# calculator.net
KiCad netlist of a schematic drawn in EAGLE
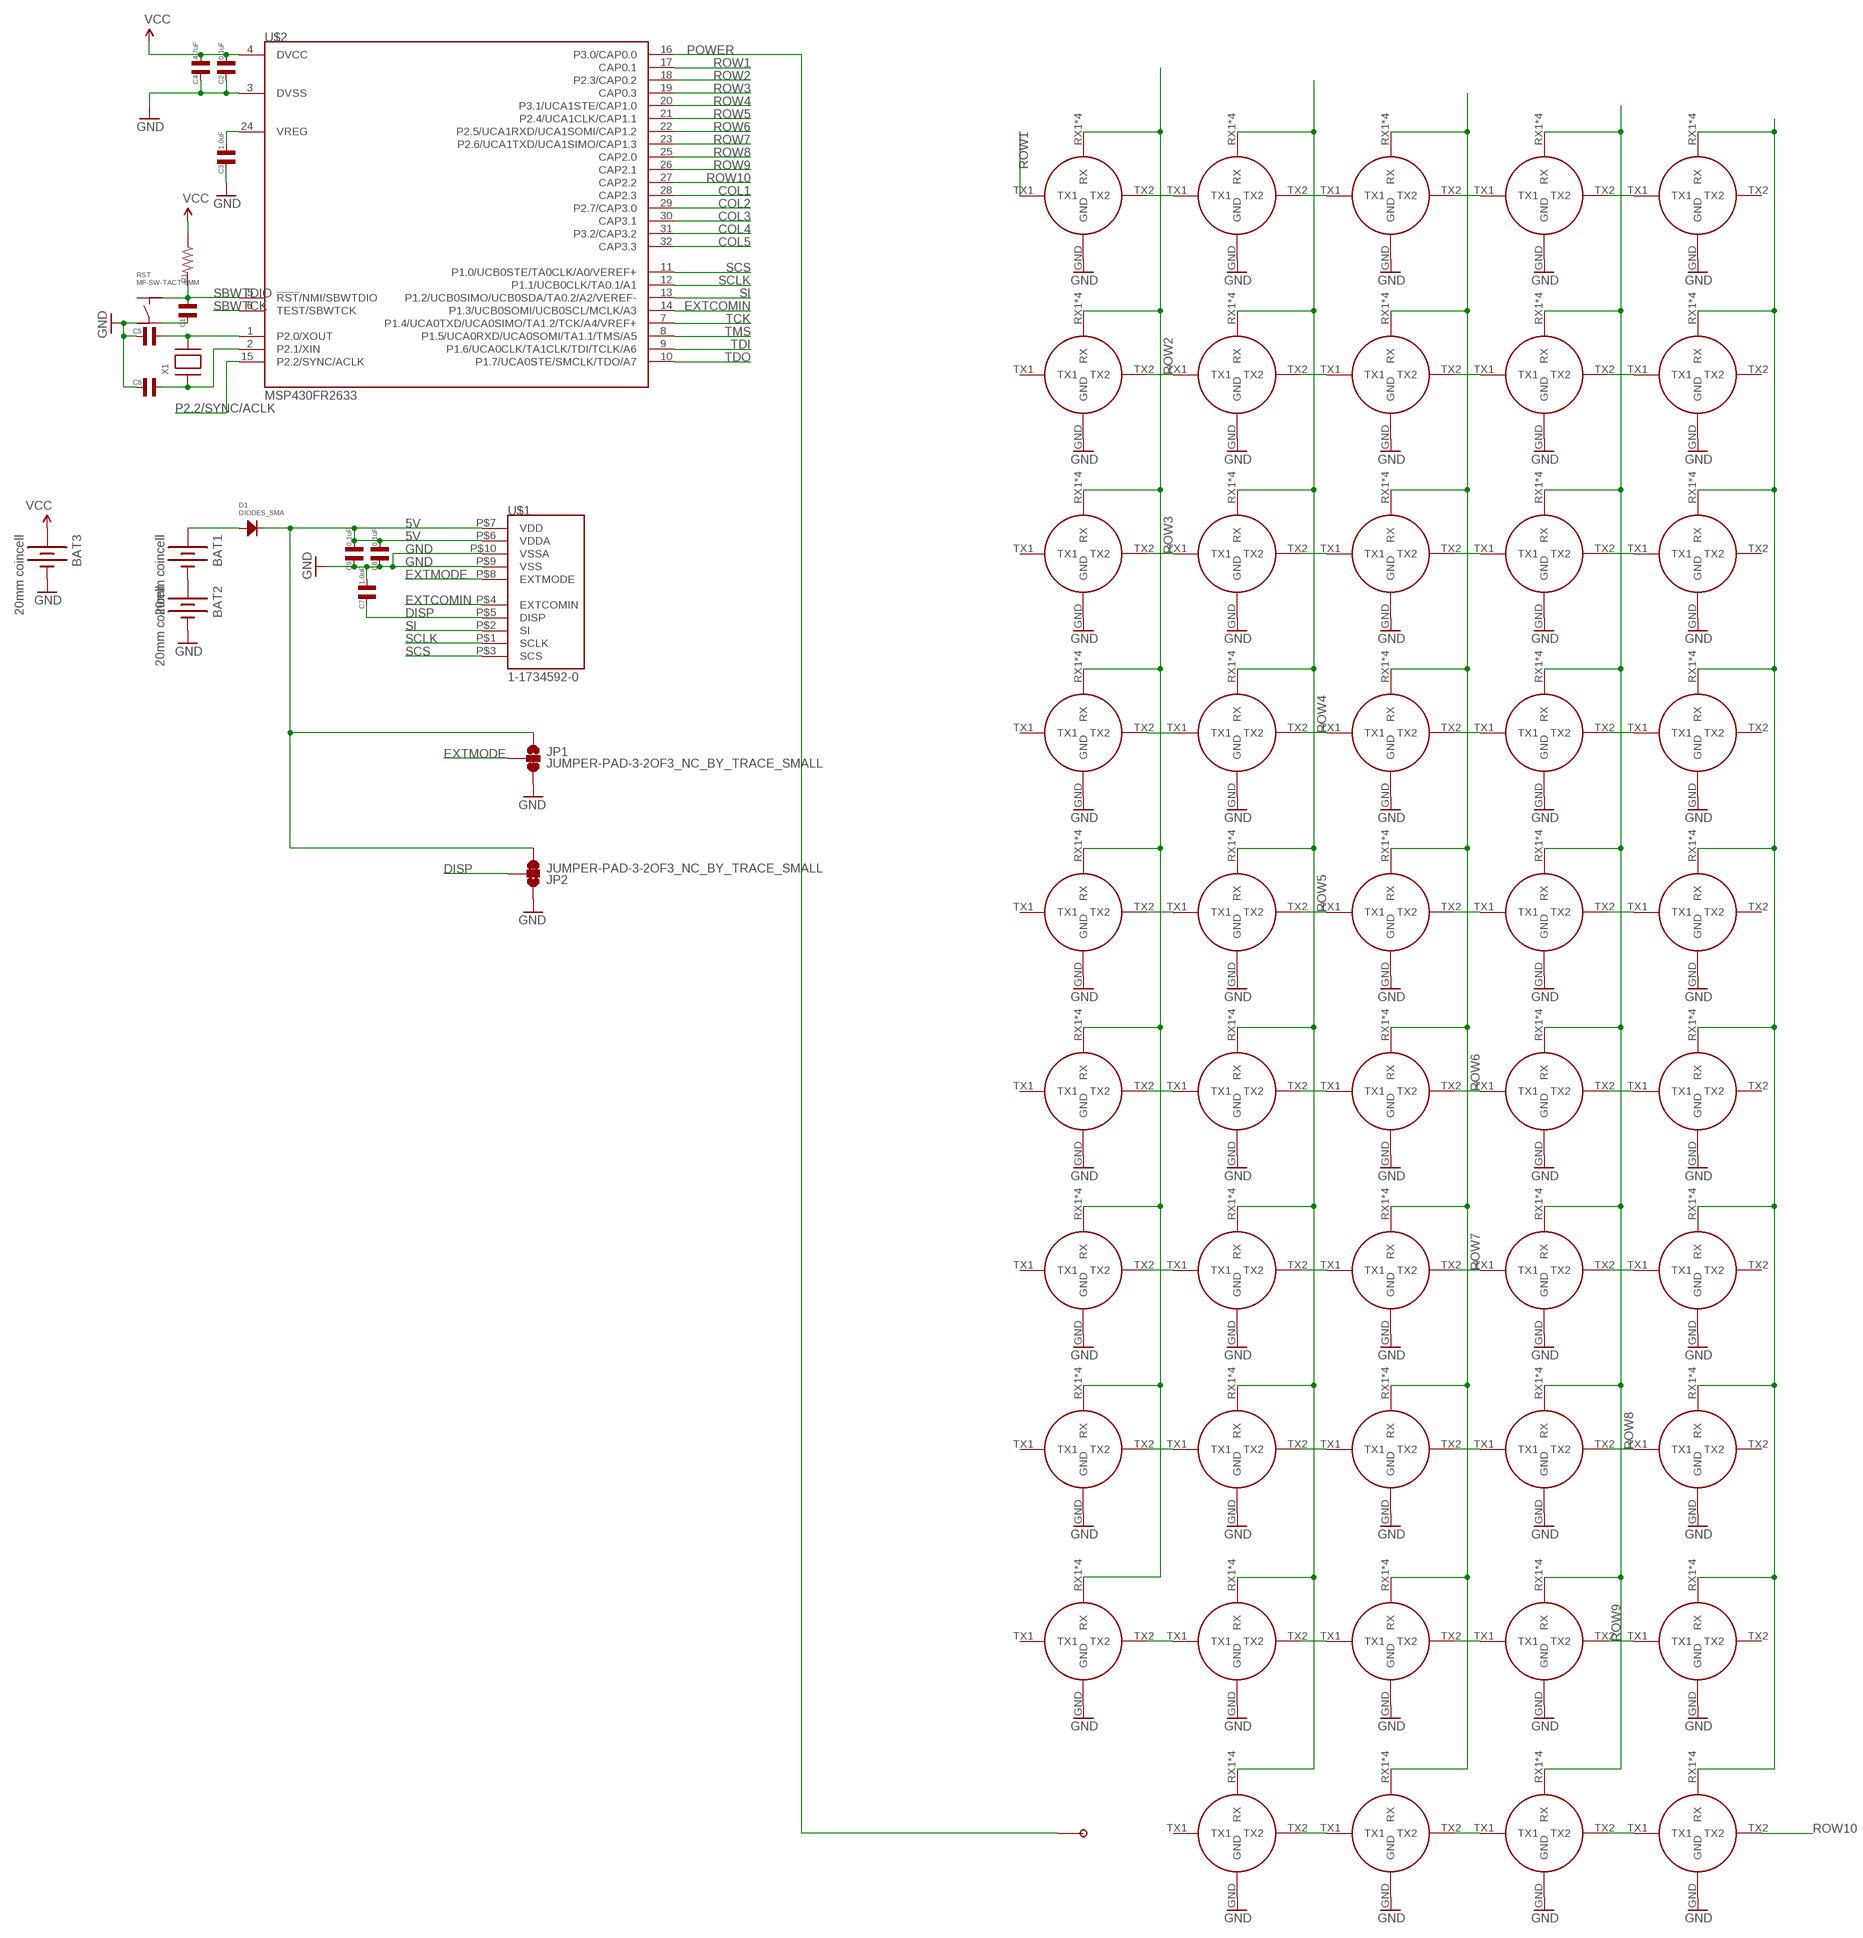
[diagram p0: schematic, sheet 1]

(export (version "E")
  (design (tool "Eeschema 10.0.6"))
  (components
    (comp (ref "BAT1")
      (value "20mm coincell")
      (footprint "eagle-import:BATTCON_20MM_4LEGS")
      (libsource (lib "eagle-import") (part "BATTERY20MM_4LEGS"))
    )
    (comp (ref "BAT2")
      (value "20mm coincell")
      (footprint "eagle-import:BATTCON_20MM_4LEGS")
      (libsource (lib "eagle-import") (part "BATTERY20MM_4LEGS"))
    )
    (comp (ref "BAT3")
      (value "20mm coincell")
      (footprint "eagle-import:BATTCON_20MM_4LEGS")
      (libsource (lib "eagle-import") (part "BATTERY20MM_4LEGS"))
    )
    (comp (ref "C1")
      (value "CAPACITOR_NP_0603")
      (footprint "eagle-import:C0603")
      (libsource (lib "eagle-import") (part "CAPACITOR_NP_0603"))
    )
    (comp (ref "C2")
      (value "0.1uF")
      (footprint "eagle-import:C0603")
      (libsource (lib "eagle-import") (part "CAPACITOR_NP_0603"))
    )
    (comp (ref "C3")
      (value "1.0uF")
      (footprint "eagle-import:C0603")
      (libsource (lib "eagle-import") (part "CAPACITOR_NP_0603"))
    )
    (comp (ref "C4")
      (value "4.7uF")
      (footprint "eagle-import:C0603")
      (libsource (lib "eagle-import") (part "CAPACITOR_NP_0603"))
    )
    (comp (ref "C5")
      (value "CAPACITOR_NP_0402")
      (footprint "eagle-import:C0402")
      (libsource (lib "eagle-import") (part "CAPACITOR_NP_0402"))
    )
    (comp (ref "C6")
      (value "CAPACITOR_NP_0402")
      (footprint "eagle-import:C0402")
      (libsource (lib "eagle-import") (part "CAPACITOR_NP_0402"))
    )
    (comp (ref "C7")
      (value "1.0uF")
      (footprint "eagle-import:C0603")
      (libsource (lib "eagle-import") (part "CAPACITOR_NP_0603"))
    )
    (comp (ref "C8")
      (value "0.1uF")
      (footprint "eagle-import:C0603")
      (libsource (lib "eagle-import") (part "CAPACITOR_NP_0603"))
    )
    (comp (ref "C9")
      (value "0.1uF")
      (footprint "eagle-import:C0603")
      (libsource (lib "eagle-import") (part "CAPACITOR_NP_0603"))
    )
    (comp (ref "D1")
      (value "DIODES_SMA")
      (footprint "eagle-import:SMA")
      (fields (field (name "HOUSEPART") "NO"))
      (libsource (lib "eagle-import") (part "DIODES_SMA"))
    )
    (comp (ref "JP1")
      (value "JUMPER-PAD-3-2OF3_NC_BY_TRACE_SMALL")
      (footprint "eagle-import:PAD-JUMPER-3-2OF3_NC_BY_TRACE_YES_SILK_FULL_BOX")
      (libsource (lib "eagle-import") (part "JUMPER-PAD-3-2OF3_NC_BY_TRACE_SMALL"))
    )
    (comp (ref "JP2")
      (value "JUMPER-PAD-3-2OF3_NC_BY_TRACE_SMALL")
      (footprint "eagle-import:PAD-JUMPER-3-2OF3_NC_BY_TRACE_YES_SILK_FULL_BOX")
      (libsource (lib "eagle-import") (part "JUMPER-PAD-3-2OF3_NC_BY_TRACE_SMALL"))
    )
    (comp (ref "P1")
      (value "CAPPADPAD")
      (footprint "eagle-import:CAPTOUCHBTN2")
      (libsource (lib "eagle-import") (part "CAPPADPAD"))
    )
    (comp (ref "R1")
      (value "RESISTOR_0603")
      (footprint "eagle-import:R0603")
      (libsource (lib "eagle-import") (part "RESISTOR_0603"))
    )
    (comp (ref "RST")
      (value "MF-SW-TACT-6MM")
      (footprint "eagle-import:TACT6MM")
      (fields (field (name "HOUSEPART") "YES"))
      (libsource (lib "eagle-import") (part "TACT_6MM"))
    )
    (comp (ref "U$1")
      (value "1-1734592-0")
      (footprint "eagle-import:1-1734592-0")
      (libsource (lib "eagle-import") (part "1-1734592-0"))
    )
    (comp (ref "U$2")
      (value "MSP430FR2633")
      (footprint "eagle-import:TSSOP32")
      (libsource (lib "eagle-import") (part "MSP430FR2633"))
    )
    (comp (ref "U$3")
      (value "CAPTOUCH")
      (footprint "eagle-import:CAPTOUCHBTN")
      (libsource (lib "eagle-import") (part "CAPTOUCH"))
    )
    (comp (ref "U$4")
      (value "CAPTOUCH")
      (footprint "eagle-import:CAPTOUCHBTN")
      (libsource (lib "eagle-import") (part "CAPTOUCH"))
    )
    (comp (ref "U$5")
      (value "CAPTOUCH")
      (footprint "eagle-import:CAPTOUCHBTN")
      (libsource (lib "eagle-import") (part "CAPTOUCH"))
    )
    (comp (ref "U$6")
      (value "CAPTOUCH")
      (footprint "eagle-import:CAPTOUCHBTN")
      (libsource (lib "eagle-import") (part "CAPTOUCH"))
    )
    (comp (ref "U$7")
      (value "CAPTOUCH")
      (footprint "eagle-import:CAPTOUCHBTN")
      (libsource (lib "eagle-import") (part "CAPTOUCH"))
    )
    (comp (ref "U$8")
      (value "CAPTOUCH")
      (footprint "eagle-import:CAPTOUCHBTN")
      (libsource (lib "eagle-import") (part "CAPTOUCH"))
    )
    (comp (ref "U$9")
      (value "CAPTOUCH")
      (footprint "eagle-import:CAPTOUCHBTN")
      (libsource (lib "eagle-import") (part "CAPTOUCH"))
    )
    (comp (ref "U$10")
      (value "CAPTOUCH")
      (footprint "eagle-import:CAPTOUCHBTN")
      (libsource (lib "eagle-import") (part "CAPTOUCH"))
    )
    (comp (ref "U$11")
      (value "CAPTOUCH")
      (footprint "eagle-import:CAPTOUCHBTN")
      (libsource (lib "eagle-import") (part "CAPTOUCH"))
    )
    (comp (ref "U$12")
      (value "CAPTOUCH")
      (footprint "eagle-import:CAPTOUCHBTN")
      (libsource (lib "eagle-import") (part "CAPTOUCH"))
    )
    (comp (ref "U$13")
      (value "CAPTOUCH")
      (footprint "eagle-import:CAPTOUCHBTN")
      (libsource (lib "eagle-import") (part "CAPTOUCH"))
    )
    (comp (ref "U$14")
      (value "CAPTOUCH")
      (footprint "eagle-import:CAPTOUCHBTN")
      (libsource (lib "eagle-import") (part "CAPTOUCH"))
    )
    (comp (ref "U$15")
      (value "CAPTOUCH")
      (footprint "eagle-import:CAPTOUCHBTN")
      (libsource (lib "eagle-import") (part "CAPTOUCH"))
    )
    (comp (ref "U$16")
      (value "CAPTOUCH")
      (footprint "eagle-import:CAPTOUCHBTN")
      (libsource (lib "eagle-import") (part "CAPTOUCH"))
    )
    (comp (ref "U$17")
      (value "CAPTOUCH")
      (footprint "eagle-import:CAPTOUCHBTN")
      (libsource (lib "eagle-import") (part "CAPTOUCH"))
    )
    (comp (ref "U$18")
      (value "CAPTOUCH")
      (footprint "eagle-import:CAPTOUCHBTN")
      (libsource (lib "eagle-import") (part "CAPTOUCH"))
    )
    (comp (ref "U$19")
      (value "CAPTOUCH")
      (footprint "eagle-import:CAPTOUCHBTN")
      (libsource (lib "eagle-import") (part "CAPTOUCH"))
    )
    (comp (ref "U$20")
      (value "CAPTOUCH")
      (footprint "eagle-import:CAPTOUCHBTN")
      (libsource (lib "eagle-import") (part "CAPTOUCH"))
    )
    (comp (ref "U$21")
      (value "CAPTOUCH")
      (footprint "eagle-import:CAPTOUCHBTN")
      (libsource (lib "eagle-import") (part "CAPTOUCH"))
    )
    (comp (ref "U$22")
      (value "CAPTOUCH")
      (footprint "eagle-import:CAPTOUCHBTN")
      (libsource (lib "eagle-import") (part "CAPTOUCH"))
    )
    (comp (ref "U$23")
      (value "CAPTOUCH")
      (footprint "eagle-import:CAPTOUCHBTN")
      (libsource (lib "eagle-import") (part "CAPTOUCH"))
    )
    (comp (ref "U$24")
      (value "CAPTOUCH")
      (footprint "eagle-import:CAPTOUCHBTN")
      (libsource (lib "eagle-import") (part "CAPTOUCH"))
    )
    (comp (ref "U$25")
      (value "CAPTOUCH")
      (footprint "eagle-import:CAPTOUCHBTN")
      (libsource (lib "eagle-import") (part "CAPTOUCH"))
    )
    (comp (ref "U$26")
      (value "CAPTOUCH")
      (footprint "eagle-import:CAPTOUCHBTN")
      (libsource (lib "eagle-import") (part "CAPTOUCH"))
    )
    (comp (ref "U$27")
      (value "CAPTOUCH")
      (footprint "eagle-import:CAPTOUCHBTN")
      (libsource (lib "eagle-import") (part "CAPTOUCH"))
    )
    (comp (ref "U$28")
      (value "CAPTOUCH")
      (footprint "eagle-import:CAPTOUCHBTN")
      (libsource (lib "eagle-import") (part "CAPTOUCH"))
    )
    (comp (ref "U$29")
      (value "CAPTOUCH")
      (footprint "eagle-import:CAPTOUCHBTN")
      (libsource (lib "eagle-import") (part "CAPTOUCH"))
    )
    (comp (ref "U$30")
      (value "CAPTOUCH")
      (footprint "eagle-import:CAPTOUCHBTN")
      (libsource (lib "eagle-import") (part "CAPTOUCH"))
    )
    (comp (ref "U$31")
      (value "CAPTOUCH")
      (footprint "eagle-import:CAPTOUCHBTN")
      (libsource (lib "eagle-import") (part "CAPTOUCH"))
    )
    (comp (ref "U$32")
      (value "CAPTOUCH")
      (footprint "eagle-import:CAPTOUCHBTN")
      (libsource (lib "eagle-import") (part "CAPTOUCH"))
    )
    (comp (ref "U$33")
      (value "CAPTOUCH")
      (footprint "eagle-import:CAPTOUCHBTN")
      (libsource (lib "eagle-import") (part "CAPTOUCH"))
    )
    (comp (ref "U$34")
      (value "CAPTOUCH")
      (footprint "eagle-import:CAPTOUCHBTN")
      (libsource (lib "eagle-import") (part "CAPTOUCH"))
    )
    (comp (ref "U$35")
      (value "CAPTOUCH")
      (footprint "eagle-import:CAPTOUCHBTN")
      (libsource (lib "eagle-import") (part "CAPTOUCH"))
    )
    (comp (ref "U$36")
      (value "CAPTOUCH")
      (footprint "eagle-import:CAPTOUCHBTN")
      (libsource (lib "eagle-import") (part "CAPTOUCH"))
    )
    (comp (ref "U$37")
      (value "CAPTOUCH")
      (footprint "eagle-import:CAPTOUCHBTN")
      (libsource (lib "eagle-import") (part "CAPTOUCH"))
    )
    (comp (ref "U$38")
      (value "CAPTOUCH")
      (footprint "eagle-import:CAPTOUCHBTN")
      (libsource (lib "eagle-import") (part "CAPTOUCH"))
    )
    (comp (ref "U$39")
      (value "CAPTOUCH")
      (footprint "eagle-import:CAPTOUCHBTN")
      (libsource (lib "eagle-import") (part "CAPTOUCH"))
    )
    (comp (ref "U$40")
      (value "CAPTOUCH")
      (footprint "eagle-import:CAPTOUCHBTN")
      (libsource (lib "eagle-import") (part "CAPTOUCH"))
    )
    (comp (ref "U$41")
      (value "CAPTOUCH")
      (footprint "eagle-import:CAPTOUCHBTN")
      (libsource (lib "eagle-import") (part "CAPTOUCH"))
    )
    (comp (ref "U$42")
      (value "CAPTOUCH")
      (footprint "eagle-import:CAPTOUCHBTN")
      (libsource (lib "eagle-import") (part "CAPTOUCH"))
    )
    (comp (ref "U$43")
      (value "CAPTOUCH")
      (footprint "eagle-import:CAPTOUCHBTN")
      (libsource (lib "eagle-import") (part "CAPTOUCH"))
    )
    (comp (ref "U$44")
      (value "CAPTOUCH")
      (footprint "eagle-import:CAPTOUCHBTN")
      (libsource (lib "eagle-import") (part "CAPTOUCH"))
    )
    (comp (ref "U$45")
      (value "CAPTOUCH")
      (footprint "eagle-import:CAPTOUCHBTN")
      (libsource (lib "eagle-import") (part "CAPTOUCH"))
    )
    (comp (ref "U$46")
      (value "CAPTOUCH")
      (footprint "eagle-import:CAPTOUCHBTN")
      (libsource (lib "eagle-import") (part "CAPTOUCH"))
    )
    (comp (ref "U$47")
      (value "CAPTOUCH")
      (footprint "eagle-import:CAPTOUCHBTN")
      (libsource (lib "eagle-import") (part "CAPTOUCH"))
    )
    (comp (ref "U$48")
      (value "CAPTOUCH")
      (footprint "eagle-import:CAPTOUCHBTN")
      (libsource (lib "eagle-import") (part "CAPTOUCH"))
    )
    (comp (ref "U$49")
      (value "CAPTOUCH")
      (footprint "eagle-import:CAPTOUCHBTN")
      (libsource (lib "eagle-import") (part "CAPTOUCH"))
    )
    (comp (ref "U$50")
      (value "CAPTOUCH")
      (footprint "eagle-import:CAPTOUCHBTN")
      (libsource (lib "eagle-import") (part "CAPTOUCH"))
    )
    (comp (ref "U$51")
      (value "CAPTOUCH")
      (footprint "eagle-import:CAPTOUCHBTN")
      (libsource (lib "eagle-import") (part "CAPTOUCH"))
    )
    (comp (ref "X1")
      (value "XTAL-3.2X1.5")
      (footprint "eagle-import:XTAL3215")
      (libsource (lib "eagle-import") (part "XTAL-3.2X1.5"))
    )
  )
  (nets
    (net (code "1") (name "/5V") (class "Default")
      (node (ref "C8") (pin "P$1") (pinfunction "P$1_P$1") (pintype "passive"))
      (node (ref "C9") (pin "P$1") (pinfunction "P$1_P$1") (pintype "passive"))
      (node (ref "D1") (pin "CATHODE") (pinfunction "CATHODE_CATHODE") (pintype "bidirectional"))
      (node (ref "JP1") (pin "1") (pinfunction "1_1") (pintype "passive"))
      (node (ref "JP2") (pin "3") (pinfunction "3_3") (pintype "passive"))
      (node (ref "U$1") (pin "P$6") (pinfunction "VDDA_P$6") (pintype "bidirectional"))
      (node (ref "U$1") (pin "P$7") (pinfunction "VDD_P$7") (pintype "bidirectional"))
    )
    (net (code "2") (name "/COL1") (class "Default")
      (node (ref "U$13") (pin "RX1") (pinfunction "RX_RX1") (pintype "bidirectional"))
      (node (ref "U$13") (pin "RX2") (pinfunction "RX_RX2") (pintype "bidirectional"))
      (node (ref "U$13") (pin "RX3") (pinfunction "RX_RX3") (pintype "bidirectional"))
      (node (ref "U$13") (pin "RX4") (pinfunction "RX_RX4") (pintype "bidirectional"))
      (node (ref "U$18") (pin "RX1") (pinfunction "RX_RX1") (pintype "bidirectional"))
      (node (ref "U$18") (pin "RX2") (pinfunction "RX_RX2") (pintype "bidirectional"))
      (node (ref "U$18") (pin "RX3") (pinfunction "RX_RX3") (pintype "bidirectional"))
      (node (ref "U$18") (pin "RX4") (pinfunction "RX_RX4") (pintype "bidirectional"))
      (node (ref "U$2") (pin "28") (pinfunction "CAP2.3_28") (pintype "bidirectional"))
      (node (ref "U$23") (pin "RX1") (pinfunction "RX_RX1") (pintype "bidirectional"))
      (node (ref "U$23") (pin "RX2") (pinfunction "RX_RX2") (pintype "bidirectional"))
      (node (ref "U$23") (pin "RX3") (pinfunction "RX_RX3") (pintype "bidirectional"))
      (node (ref "U$23") (pin "RX4") (pinfunction "RX_RX4") (pintype "bidirectional"))
      (node (ref "U$28") (pin "RX1") (pinfunction "RX_RX1") (pintype "bidirectional"))
      (node (ref "U$28") (pin "RX2") (pinfunction "RX_RX2") (pintype "bidirectional"))
      (node (ref "U$28") (pin "RX3") (pinfunction "RX_RX3") (pintype "bidirectional"))
      (node (ref "U$28") (pin "RX4") (pinfunction "RX_RX4") (pintype "bidirectional"))
      (node (ref "U$3") (pin "RX1") (pinfunction "RX_RX1") (pintype "bidirectional"))
      (node (ref "U$3") (pin "RX2") (pinfunction "RX_RX2") (pintype "bidirectional"))
      (node (ref "U$3") (pin "RX3") (pinfunction "RX_RX3") (pintype "bidirectional"))
      (node (ref "U$3") (pin "RX4") (pinfunction "RX_RX4") (pintype "bidirectional"))
      (node (ref "U$33") (pin "RX1") (pinfunction "RX_RX1") (pintype "bidirectional"))
      (node (ref "U$33") (pin "RX2") (pinfunction "RX_RX2") (pintype "bidirectional"))
      (node (ref "U$33") (pin "RX3") (pinfunction "RX_RX3") (pintype "bidirectional"))
      (node (ref "U$33") (pin "RX4") (pinfunction "RX_RX4") (pintype "bidirectional"))
      (node (ref "U$38") (pin "RX1") (pinfunction "RX_RX1") (pintype "bidirectional"))
      (node (ref "U$38") (pin "RX2") (pinfunction "RX_RX2") (pintype "bidirectional"))
      (node (ref "U$38") (pin "RX3") (pinfunction "RX_RX3") (pintype "bidirectional"))
      (node (ref "U$38") (pin "RX4") (pinfunction "RX_RX4") (pintype "bidirectional"))
      (node (ref "U$43") (pin "RX1") (pinfunction "RX_RX1") (pintype "bidirectional"))
      (node (ref "U$43") (pin "RX2") (pinfunction "RX_RX2") (pintype "bidirectional"))
      (node (ref "U$43") (pin "RX3") (pinfunction "RX_RX3") (pintype "bidirectional"))
      (node (ref "U$43") (pin "RX4") (pinfunction "RX_RX4") (pintype "bidirectional"))
      (node (ref "U$8") (pin "RX1") (pinfunction "RX_RX1") (pintype "bidirectional"))
      (node (ref "U$8") (pin "RX2") (pinfunction "RX_RX2") (pintype "bidirectional"))
      (node (ref "U$8") (pin "RX3") (pinfunction "RX_RX3") (pintype "bidirectional"))
      (node (ref "U$8") (pin "RX4") (pinfunction "RX_RX4") (pintype "bidirectional"))
    )
    (net (code "3") (name "/COL2") (class "Default")
      (node (ref "U$14") (pin "RX1") (pinfunction "RX_RX1") (pintype "bidirectional"))
      (node (ref "U$14") (pin "RX2") (pinfunction "RX_RX2") (pintype "bidirectional"))
      (node (ref "U$14") (pin "RX3") (pinfunction "RX_RX3") (pintype "bidirectional"))
      (node (ref "U$14") (pin "RX4") (pinfunction "RX_RX4") (pintype "bidirectional"))
      (node (ref "U$19") (pin "RX1") (pinfunction "RX_RX1") (pintype "bidirectional"))
      (node (ref "U$19") (pin "RX2") (pinfunction "RX_RX2") (pintype "bidirectional"))
      (node (ref "U$19") (pin "RX3") (pinfunction "RX_RX3") (pintype "bidirectional"))
      (node (ref "U$19") (pin "RX4") (pinfunction "RX_RX4") (pintype "bidirectional"))
      (node (ref "U$2") (pin "29") (pinfunction "P2.7/CAP3.0_29") (pintype "bidirectional"))
      (node (ref "U$24") (pin "RX1") (pinfunction "RX_RX1") (pintype "bidirectional"))
      (node (ref "U$24") (pin "RX2") (pinfunction "RX_RX2") (pintype "bidirectional"))
      (node (ref "U$24") (pin "RX3") (pinfunction "RX_RX3") (pintype "bidirectional"))
      (node (ref "U$24") (pin "RX4") (pinfunction "RX_RX4") (pintype "bidirectional"))
      (node (ref "U$29") (pin "RX1") (pinfunction "RX_RX1") (pintype "bidirectional"))
      (node (ref "U$29") (pin "RX2") (pinfunction "RX_RX2") (pintype "bidirectional"))
      (node (ref "U$29") (pin "RX3") (pinfunction "RX_RX3") (pintype "bidirectional"))
      (node (ref "U$29") (pin "RX4") (pinfunction "RX_RX4") (pintype "bidirectional"))
      (node (ref "U$34") (pin "RX1") (pinfunction "RX_RX1") (pintype "bidirectional"))
      (node (ref "U$34") (pin "RX2") (pinfunction "RX_RX2") (pintype "bidirectional"))
      (node (ref "U$34") (pin "RX3") (pinfunction "RX_RX3") (pintype "bidirectional"))
      (node (ref "U$34") (pin "RX4") (pinfunction "RX_RX4") (pintype "bidirectional"))
      (node (ref "U$39") (pin "RX1") (pinfunction "RX_RX1") (pintype "bidirectional"))
      (node (ref "U$39") (pin "RX2") (pinfunction "RX_RX2") (pintype "bidirectional"))
      (node (ref "U$39") (pin "RX3") (pinfunction "RX_RX3") (pintype "bidirectional"))
      (node (ref "U$39") (pin "RX4") (pinfunction "RX_RX4") (pintype "bidirectional"))
      (node (ref "U$4") (pin "RX1") (pinfunction "RX_RX1") (pintype "bidirectional"))
      (node (ref "U$4") (pin "RX2") (pinfunction "RX_RX2") (pintype "bidirectional"))
      (node (ref "U$4") (pin "RX3") (pinfunction "RX_RX3") (pintype "bidirectional"))
      (node (ref "U$4") (pin "RX4") (pinfunction "RX_RX4") (pintype "bidirectional"))
      (node (ref "U$44") (pin "RX1") (pinfunction "RX_RX1") (pintype "bidirectional"))
      (node (ref "U$44") (pin "RX2") (pinfunction "RX_RX2") (pintype "bidirectional"))
      (node (ref "U$44") (pin "RX3") (pinfunction "RX_RX3") (pintype "bidirectional"))
      (node (ref "U$44") (pin "RX4") (pinfunction "RX_RX4") (pintype "bidirectional"))
      (node (ref "U$48") (pin "RX1") (pinfunction "RX_RX1") (pintype "bidirectional"))
      (node (ref "U$48") (pin "RX2") (pinfunction "RX_RX2") (pintype "bidirectional"))
      (node (ref "U$48") (pin "RX3") (pinfunction "RX_RX3") (pintype "bidirectional"))
      (node (ref "U$48") (pin "RX4") (pinfunction "RX_RX4") (pintype "bidirectional"))
      (node (ref "U$9") (pin "RX1") (pinfunction "RX_RX1") (pintype "bidirectional"))
      (node (ref "U$9") (pin "RX2") (pinfunction "RX_RX2") (pintype "bidirectional"))
      (node (ref "U$9") (pin "RX3") (pinfunction "RX_RX3") (pintype "bidirectional"))
      (node (ref "U$9") (pin "RX4") (pinfunction "RX_RX4") (pintype "bidirectional"))
    )
    (net (code "4") (name "/COL3") (class "Default")
      (node (ref "U$10") (pin "RX1") (pinfunction "RX_RX1") (pintype "bidirectional"))
      (node (ref "U$10") (pin "RX2") (pinfunction "RX_RX2") (pintype "bidirectional"))
      (node (ref "U$10") (pin "RX3") (pinfunction "RX_RX3") (pintype "bidirectional"))
      (node (ref "U$10") (pin "RX4") (pinfunction "RX_RX4") (pintype "bidirectional"))
      (node (ref "U$15") (pin "RX1") (pinfunction "RX_RX1") (pintype "bidirectional"))
      (node (ref "U$15") (pin "RX2") (pinfunction "RX_RX2") (pintype "bidirectional"))
      (node (ref "U$15") (pin "RX3") (pinfunction "RX_RX3") (pintype "bidirectional"))
      (node (ref "U$15") (pin "RX4") (pinfunction "RX_RX4") (pintype "bidirectional"))
      (node (ref "U$2") (pin "30") (pinfunction "CAP3.1_30") (pintype "bidirectional"))
      (node (ref "U$20") (pin "RX1") (pinfunction "RX_RX1") (pintype "bidirectional"))
      (node (ref "U$20") (pin "RX2") (pinfunction "RX_RX2") (pintype "bidirectional"))
      (node (ref "U$20") (pin "RX3") (pinfunction "RX_RX3") (pintype "bidirectional"))
      (node (ref "U$20") (pin "RX4") (pinfunction "RX_RX4") (pintype "bidirectional"))
      (node (ref "U$25") (pin "RX1") (pinfunction "RX_RX1") (pintype "bidirectional"))
      (node (ref "U$25") (pin "RX2") (pinfunction "RX_RX2") (pintype "bidirectional"))
      (node (ref "U$25") (pin "RX3") (pinfunction "RX_RX3") (pintype "bidirectional"))
      (node (ref "U$25") (pin "RX4") (pinfunction "RX_RX4") (pintype "bidirectional"))
      (node (ref "U$30") (pin "RX1") (pinfunction "RX_RX1") (pintype "bidirectional"))
      (node (ref "U$30") (pin "RX2") (pinfunction "RX_RX2") (pintype "bidirectional"))
      (node (ref "U$30") (pin "RX3") (pinfunction "RX_RX3") (pintype "bidirectional"))
      (node (ref "U$30") (pin "RX4") (pinfunction "RX_RX4") (pintype "bidirectional"))
      (node (ref "U$35") (pin "RX1") (pinfunction "RX_RX1") (pintype "bidirectional"))
      (node (ref "U$35") (pin "RX2") (pinfunction "RX_RX2") (pintype "bidirectional"))
      (node (ref "U$35") (pin "RX3") (pinfunction "RX_RX3") (pintype "bidirectional"))
      (node (ref "U$35") (pin "RX4") (pinfunction "RX_RX4") (pintype "bidirectional"))
      (node (ref "U$40") (pin "RX1") (pinfunction "RX_RX1") (pintype "bidirectional"))
      (node (ref "U$40") (pin "RX2") (pinfunction "RX_RX2") (pintype "bidirectional"))
      (node (ref "U$40") (pin "RX3") (pinfunction "RX_RX3") (pintype "bidirectional"))
      (node (ref "U$40") (pin "RX4") (pinfunction "RX_RX4") (pintype "bidirectional"))
      (node (ref "U$45") (pin "RX1") (pinfunction "RX_RX1") (pintype "bidirectional"))
      (node (ref "U$45") (pin "RX2") (pinfunction "RX_RX2") (pintype "bidirectional"))
      (node (ref "U$45") (pin "RX3") (pinfunction "RX_RX3") (pintype "bidirectional"))
      (node (ref "U$45") (pin "RX4") (pinfunction "RX_RX4") (pintype "bidirectional"))
      (node (ref "U$49") (pin "RX1") (pinfunction "RX_RX1") (pintype "bidirectional"))
      (node (ref "U$49") (pin "RX2") (pinfunction "RX_RX2") (pintype "bidirectional"))
      (node (ref "U$49") (pin "RX3") (pinfunction "RX_RX3") (pintype "bidirectional"))
      (node (ref "U$49") (pin "RX4") (pinfunction "RX_RX4") (pintype "bidirectional"))
      (node (ref "U$5") (pin "RX1") (pinfunction "RX_RX1") (pintype "bidirectional"))
      (node (ref "U$5") (pin "RX2") (pinfunction "RX_RX2") (pintype "bidirectional"))
      (node (ref "U$5") (pin "RX3") (pinfunction "RX_RX3") (pintype "bidirectional"))
      (node (ref "U$5") (pin "RX4") (pinfunction "RX_RX4") (pintype "bidirectional"))
    )
    (net (code "5") (name "/COL4") (class "Default")
      (node (ref "U$11") (pin "RX1") (pinfunction "RX_RX1") (pintype "bidirectional"))
      (node (ref "U$11") (pin "RX2") (pinfunction "RX_RX2") (pintype "bidirectional"))
      (node (ref "U$11") (pin "RX3") (pinfunction "RX_RX3") (pintype "bidirectional"))
      (node (ref "U$11") (pin "RX4") (pinfunction "RX_RX4") (pintype "bidirectional"))
      (node (ref "U$16") (pin "RX1") (pinfunction "RX_RX1") (pintype "bidirectional"))
      (node (ref "U$16") (pin "RX2") (pinfunction "RX_RX2") (pintype "bidirectional"))
      (node (ref "U$16") (pin "RX3") (pinfunction "RX_RX3") (pintype "bidirectional"))
      (node (ref "U$16") (pin "RX4") (pinfunction "RX_RX4") (pintype "bidirectional"))
      (node (ref "U$2") (pin "31") (pinfunction "P3.2/CAP3.2_31") (pintype "bidirectional"))
      (node (ref "U$21") (pin "RX1") (pinfunction "RX_RX1") (pintype "bidirectional"))
      (node (ref "U$21") (pin "RX2") (pinfunction "RX_RX2") (pintype "bidirectional"))
      (node (ref "U$21") (pin "RX3") (pinfunction "RX_RX3") (pintype "bidirectional"))
      (node (ref "U$21") (pin "RX4") (pinfunction "RX_RX4") (pintype "bidirectional"))
      (node (ref "U$26") (pin "RX1") (pinfunction "RX_RX1") (pintype "bidirectional"))
      (node (ref "U$26") (pin "RX2") (pinfunction "RX_RX2") (pintype "bidirectional"))
      (node (ref "U$26") (pin "RX3") (pinfunction "RX_RX3") (pintype "bidirectional"))
      (node (ref "U$26") (pin "RX4") (pinfunction "RX_RX4") (pintype "bidirectional"))
      (node (ref "U$31") (pin "RX1") (pinfunction "RX_RX1") (pintype "bidirectional"))
      (node (ref "U$31") (pin "RX2") (pinfunction "RX_RX2") (pintype "bidirectional"))
      (node (ref "U$31") (pin "RX3") (pinfunction "RX_RX3") (pintype "bidirectional"))
      (node (ref "U$31") (pin "RX4") (pinfunction "RX_RX4") (pintype "bidirectional"))
      (node (ref "U$36") (pin "RX1") (pinfunction "RX_RX1") (pintype "bidirectional"))
      (node (ref "U$36") (pin "RX2") (pinfunction "RX_RX2") (pintype "bidirectional"))
      (node (ref "U$36") (pin "RX3") (pinfunction "RX_RX3") (pintype "bidirectional"))
      (node (ref "U$36") (pin "RX4") (pinfunction "RX_RX4") (pintype "bidirectional"))
      (node (ref "U$41") (pin "RX1") (pinfunction "RX_RX1") (pintype "bidirectional"))
      (node (ref "U$41") (pin "RX2") (pinfunction "RX_RX2") (pintype "bidirectional"))
      (node (ref "U$41") (pin "RX3") (pinfunction "RX_RX3") (pintype "bidirectional"))
      (node (ref "U$41") (pin "RX4") (pinfunction "RX_RX4") (pintype "bidirectional"))
      (node (ref "U$46") (pin "RX1") (pinfunction "RX_RX1") (pintype "bidirectional"))
      (node (ref "U$46") (pin "RX2") (pinfunction "RX_RX2") (pintype "bidirectional"))
      (node (ref "U$46") (pin "RX3") (pinfunction "RX_RX3") (pintype "bidirectional"))
      (node (ref "U$46") (pin "RX4") (pinfunction "RX_RX4") (pintype "bidirectional"))
      (node (ref "U$50") (pin "RX1") (pinfunction "RX_RX1") (pintype "bidirectional"))
      (node (ref "U$50") (pin "RX2") (pinfunction "RX_RX2") (pintype "bidirectional"))
      (node (ref "U$50") (pin "RX3") (pinfunction "RX_RX3") (pintype "bidirectional"))
      (node (ref "U$50") (pin "RX4") (pinfunction "RX_RX4") (pintype "bidirectional"))
      (node (ref "U$6") (pin "RX1") (pinfunction "RX_RX1") (pintype "bidirectional"))
      (node (ref "U$6") (pin "RX2") (pinfunction "RX_RX2") (pintype "bidirectional"))
      (node (ref "U$6") (pin "RX3") (pinfunction "RX_RX3") (pintype "bidirectional"))
      (node (ref "U$6") (pin "RX4") (pinfunction "RX_RX4") (pintype "bidirectional"))
    )
    (net (code "6") (name "/COL5") (class "Default")
      (node (ref "U$12") (pin "RX1") (pinfunction "RX_RX1") (pintype "bidirectional"))
      (node (ref "U$12") (pin "RX2") (pinfunction "RX_RX2") (pintype "bidirectional"))
      (node (ref "U$12") (pin "RX3") (pinfunction "RX_RX3") (pintype "bidirectional"))
      (node (ref "U$12") (pin "RX4") (pinfunction "RX_RX4") (pintype "bidirectional"))
      (node (ref "U$17") (pin "RX1") (pinfunction "RX_RX1") (pintype "bidirectional"))
      (node (ref "U$17") (pin "RX2") (pinfunction "RX_RX2") (pintype "bidirectional"))
      (node (ref "U$17") (pin "RX3") (pinfunction "RX_RX3") (pintype "bidirectional"))
      (node (ref "U$17") (pin "RX4") (pinfunction "RX_RX4") (pintype "bidirectional"))
      (node (ref "U$2") (pin "32") (pinfunction "CAP3.3_32") (pintype "bidirectional"))
      (node (ref "U$22") (pin "RX1") (pinfunction "RX_RX1") (pintype "bidirectional"))
      (node (ref "U$22") (pin "RX2") (pinfunction "RX_RX2") (pintype "bidirectional"))
      (node (ref "U$22") (pin "RX3") (pinfunction "RX_RX3") (pintype "bidirectional"))
      (node (ref "U$22") (pin "RX4") (pinfunction "RX_RX4") (pintype "bidirectional"))
      (node (ref "U$27") (pin "RX1") (pinfunction "RX_RX1") (pintype "bidirectional"))
      (node (ref "U$27") (pin "RX2") (pinfunction "RX_RX2") (pintype "bidirectional"))
      (node (ref "U$27") (pin "RX3") (pinfunction "RX_RX3") (pintype "bidirectional"))
      (node (ref "U$27") (pin "RX4") (pinfunction "RX_RX4") (pintype "bidirectional"))
      (node (ref "U$32") (pin "RX1") (pinfunction "RX_RX1") (pintype "bidirectional"))
      (node (ref "U$32") (pin "RX2") (pinfunction "RX_RX2") (pintype "bidirectional"))
      (node (ref "U$32") (pin "RX3") (pinfunction "RX_RX3") (pintype "bidirectional"))
      (node (ref "U$32") (pin "RX4") (pinfunction "RX_RX4") (pintype "bidirectional"))
      (node (ref "U$37") (pin "RX1") (pinfunction "RX_RX1") (pintype "bidirectional"))
      (node (ref "U$37") (pin "RX2") (pinfunction "RX_RX2") (pintype "bidirectional"))
      (node (ref "U$37") (pin "RX3") (pinfunction "RX_RX3") (pintype "bidirectional"))
      (node (ref "U$37") (pin "RX4") (pinfunction "RX_RX4") (pintype "bidirectional"))
      (node (ref "U$42") (pin "RX1") (pinfunction "RX_RX1") (pintype "bidirectional"))
      (node (ref "U$42") (pin "RX2") (pinfunction "RX_RX2") (pintype "bidirectional"))
      (node (ref "U$42") (pin "RX3") (pinfunction "RX_RX3") (pintype "bidirectional"))
      (node (ref "U$42") (pin "RX4") (pinfunction "RX_RX4") (pintype "bidirectional"))
      (node (ref "U$47") (pin "RX1") (pinfunction "RX_RX1") (pintype "bidirectional"))
      (node (ref "U$47") (pin "RX2") (pinfunction "RX_RX2") (pintype "bidirectional"))
      (node (ref "U$47") (pin "RX3") (pinfunction "RX_RX3") (pintype "bidirectional"))
      (node (ref "U$47") (pin "RX4") (pinfunction "RX_RX4") (pintype "bidirectional"))
      (node (ref "U$51") (pin "RX1") (pinfunction "RX_RX1") (pintype "bidirectional"))
      (node (ref "U$51") (pin "RX2") (pinfunction "RX_RX2") (pintype "bidirectional"))
      (node (ref "U$51") (pin "RX3") (pinfunction "RX_RX3") (pintype "bidirectional"))
      (node (ref "U$51") (pin "RX4") (pinfunction "RX_RX4") (pintype "bidirectional"))
      (node (ref "U$7") (pin "RX1") (pinfunction "RX_RX1") (pintype "bidirectional"))
      (node (ref "U$7") (pin "RX2") (pinfunction "RX_RX2") (pintype "bidirectional"))
      (node (ref "U$7") (pin "RX3") (pinfunction "RX_RX3") (pintype "bidirectional"))
      (node (ref "U$7") (pin "RX4") (pinfunction "RX_RX4") (pintype "bidirectional"))
    )
    (net (code "7") (name "/DISP") (class "Default")
      (node (ref "C7") (pin "P$2") (pinfunction "P$2_P$2") (pintype "passive"))
      (node (ref "JP2") (pin "2") (pinfunction "2_2") (pintype "passive"))
      (node (ref "U$1") (pin "P$5") (pinfunction "DISP_P$5") (pintype "bidirectional"))
    )
    (net (code "8") (name "/EXTCOMIN") (class "Default")
      (node (ref "U$1") (pin "P$4") (pinfunction "EXTCOMIN_P$4") (pintype "bidirectional"))
      (node (ref "U$2") (pin "14") (pinfunction "P1.3/UCB0SOMI/UCB0SCL/MCLK/A3_14") (pintype "bidirectional"))
    )
    (net (code "9") (name "/EXTMODE") (class "Default")
      (node (ref "JP1") (pin "2") (pinfunction "2_2") (pintype "passive"))
      (node (ref "U$1") (pin "P$8") (pinfunction "EXTMODE_P$8") (pintype "bidirectional"))
    )
    (net (code "10") (name "/P2.2{slash}SYNC{slash}ACLK") (class "Default")
      (node (ref "U$2") (pin "15") (pinfunction "P2.2/SYNC/ACLK_15") (pintype "bidirectional"))
    )
    (net (code "11") (name "/POWER") (class "Default")
      (node (ref "P1") (pin "RX") (pinfunction "P$1_RX") (pintype "bidirectional"))
      (node (ref "U$2") (pin "16") (pinfunction "P3.0/CAP0.0_16") (pintype "bidirectional"))
    )
    (net (code "12") (name "/ROW1") (class "Default")
      (node (ref "U$2") (pin "17") (pinfunction "CAP0.1_17") (pintype "bidirectional"))
      (node (ref "U$3") (pin "TX1") (pinfunction "TX1_TX1") (pintype "bidirectional"))
    )
    (net (code "13") (name "/ROW2") (class "Default")
      (node (ref "U$2") (pin "18") (pinfunction "P2.3/CAP0.2_18") (pintype "bidirectional"))
      (node (ref "U$8") (pin "TX2") (pinfunction "TX2_TX2") (pintype "bidirectional"))
      (node (ref "U$9") (pin "TX1") (pinfunction "TX1_TX1") (pintype "bidirectional"))
    )
    (net (code "14") (name "/ROW3") (class "Default")
      (node (ref "U$13") (pin "TX2") (pinfunction "TX2_TX2") (pintype "bidirectional"))
      (node (ref "U$14") (pin "TX1") (pinfunction "TX1_TX1") (pintype "bidirectional"))
      (node (ref "U$2") (pin "19") (pinfunction "CAP0.3_19") (pintype "bidirectional"))
    )
    (net (code "15") (name "/ROW4") (class "Default")
      (node (ref "U$19") (pin "TX2") (pinfunction "TX2_TX2") (pintype "bidirectional"))
      (node (ref "U$2") (pin "20") (pinfunction "P3.1/UCA1STE/CAP1.0_20") (pintype "bidirectional"))
      (node (ref "U$20") (pin "TX1") (pinfunction "TX1_TX1") (pintype "bidirectional"))
    )
    (net (code "16") (name "/ROW5") (class "Default")
      (node (ref "U$2") (pin "21") (pinfunction "P2.4/UCA1CLK/CAP1.1_21") (pintype "bidirectional"))
      (node (ref "U$24") (pin "TX2") (pinfunction "TX2_TX2") (pintype "bidirectional"))
      (node (ref "U$25") (pin "TX1") (pinfunction "TX1_TX1") (pintype "bidirectional"))
    )
    (net (code "17") (name "/ROW6") (class "Default")
      (node (ref "U$2") (pin "22") (pinfunction "P2.5/UCA1RXD/UCA1SOMI/CAP1.2_22") (pintype "bidirectional"))
      (node (ref "U$30") (pin "TX2") (pinfunction "TX2_TX2") (pintype "bidirectional"))
      (node (ref "U$31") (pin "TX1") (pinfunction "TX1_TX1") (pintype "bidirectional"))
    )
    (net (code "18") (name "/ROW7") (class "Default")
      (node (ref "U$2") (pin "23") (pinfunction "P2.6/UCA1TXD/UCA1SIMO/CAP1.3_23") (pintype "bidirectional"))
      (node (ref "U$35") (pin "TX2") (pinfunction "TX2_TX2") (pintype "bidirectional"))
      (node (ref "U$36") (pin "TX1") (pinfunction "TX1_TX1") (pintype "bidirectional"))
    )
    (net (code "19") (name "/ROW8") (class "Default")
      (node (ref "U$2") (pin "25") (pinfunction "CAP2.0_25") (pintype "bidirectional"))
      (node (ref "U$41") (pin "TX2") (pinfunction "TX2_TX2") (pintype "bidirectional"))
      (node (ref "U$42") (pin "TX1") (pinfunction "TX1_TX1") (pintype "bidirectional"))
    )
    (net (code "20") (name "/ROW9") (class "Default")
      (node (ref "U$2") (pin "26") (pinfunction "CAP2.1_26") (pintype "bidirectional"))
      (node (ref "U$46") (pin "TX2") (pinfunction "TX2_TX2") (pintype "bidirectional"))
      (node (ref "U$47") (pin "TX1") (pinfunction "TX1_TX1") (pintype "bidirectional"))
    )
    (net (code "21") (name "/ROW10") (class "Default")
      (node (ref "U$2") (pin "27") (pinfunction "CAP2.2_27") (pintype "bidirectional"))
      (node (ref "U$51") (pin "TX2") (pinfunction "TX2_TX2") (pintype "bidirectional"))
    )
    (net (code "22") (name "/SBWTCK") (class "Default")
      (node (ref "U$2") (pin "6") (pinfunction "TEST/SBWTCK_6") (pintype "bidirectional"))
    )
    (net (code "23") (name "/SBWTDIO") (class "Default")
      (node (ref "C1") (pin "P$1") (pinfunction "P$1_P$1") (pintype "passive"))
      (node (ref "R1") (pin "P$2") (pinfunction "P$2_P$2") (pintype "passive"))
      (node (ref "RST") (pin "P$2") (pinfunction "P$2_P$2") (pintype "bidirectional"))
      (node (ref "U$2") (pin "5") (pinfunction "~{RST}/NMI/SBWTDIO_5") (pintype "bidirectional"))
    )
    (net (code "24") (name "/SCLK") (class "Default")
      (node (ref "U$1") (pin "P$1") (pinfunction "SCLK_P$1") (pintype "bidirectional"))
      (node (ref "U$2") (pin "12") (pinfunction "P1.1/UCB0CLK/TA0.1/A1_12") (pintype "bidirectional"))
    )
    (net (code "25") (name "/SCS") (class "Default")
      (node (ref "U$1") (pin "P$3") (pinfunction "SCS_P$3") (pintype "bidirectional"))
      (node (ref "U$2") (pin "11") (pinfunction "P1.0/UCB0STE/TA0CLK/A0/VEREF+_11") (pintype "bidirectional"))
    )
    (net (code "26") (name "/SI") (class "Default")
      (node (ref "U$1") (pin "P$2") (pinfunction "SI_P$2") (pintype "bidirectional"))
      (node (ref "U$2") (pin "13") (pinfunction "P1.2/UCB0SIMO/UCB0SDA/TA0.2/A2/VEREF-_13") (pintype "bidirectional"))
    )
    (net (code "27") (name "/TCK") (class "Default")
      (node (ref "U$2") (pin "7") (pinfunction "P1.4/UCA0TXD/UCA0SIMO/TA1.2/TCK/A4/VREF+_7") (pintype "bidirectional"))
    )
    (net (code "28") (name "/TDI") (class "Default")
      (node (ref "U$2") (pin "9") (pinfunction "P1.6/UCA0CLK/TA1CLK/TDI/TCLK/A6_9") (pintype "bidirectional"))
    )
    (net (code "29") (name "/TDO") (class "Default")
      (node (ref "U$2") (pin "10") (pinfunction "P1.7/UCA0STE/SMCLK/TDO/A7_10") (pintype "bidirectional"))
    )
    (net (code "30") (name "/TMS") (class "Default")
      (node (ref "U$2") (pin "8") (pinfunction "P1.5/UCA0RXD/UCA0SOMI/TA1.1/TMS/A5_8") (pintype "bidirectional"))
    )
    (net (code "31") (name "GND") (class "Default")
      (node (ref "BAT2") (pin "NEGATIVE") (pinfunction "-_NEGATIVE") (pintype "power_in"))
      (node (ref "BAT3") (pin "NEGATIVE") (pinfunction "-_NEGATIVE") (pintype "power_in"))
      (node (ref "C2") (pin "P$2") (pinfunction "P$2_P$2") (pintype "passive"))
      (node (ref "C3") (pin "P$2") (pinfunction "P$2_P$2") (pintype "passive"))
      (node (ref "C4") (pin "P$2") (pinfunction "P$2_P$2") (pintype "passive"))
      (node (ref "C5") (pin "P$2") (pinfunction "P$2_P$2") (pintype "passive"))
      (node (ref "C6") (pin "P$2") (pinfunction "P$2_P$2") (pintype "passive"))
      (node (ref "C7") (pin "P$1") (pinfunction "P$1_P$1") (pintype "passive"))
      (node (ref "C8") (pin "P$2") (pinfunction "P$2_P$2") (pintype "passive"))
      (node (ref "C9") (pin "P$2") (pinfunction "P$2_P$2") (pintype "passive"))
      (node (ref "JP1") (pin "3") (pinfunction "3_3") (pintype "passive"))
      (node (ref "JP2") (pin "1") (pinfunction "1_1") (pintype "passive"))
      (node (ref "RST") (pin "P$3") (pinfunction "P$3_P$3") (pintype "bidirectional"))
      (node (ref "U$1") (pin "P$10") (pinfunction "VSSA_P$10") (pintype "bidirectional"))
      (node (ref "U$1") (pin "P$9") (pinfunction "VSS_P$9") (pintype "bidirectional"))
      (node (ref "U$10") (pin "GND") (pinfunction "GND_GND") (pintype "bidirectional"))
      (node (ref "U$11") (pin "GND") (pinfunction "GND_GND") (pintype "bidirectional"))
      (node (ref "U$12") (pin "GND") (pinfunction "GND_GND") (pintype "bidirectional"))
      (node (ref "U$13") (pin "GND") (pinfunction "GND_GND") (pintype "bidirectional"))
      (node (ref "U$14") (pin "GND") (pinfunction "GND_GND") (pintype "bidirectional"))
      (node (ref "U$15") (pin "GND") (pinfunction "GND_GND") (pintype "bidirectional"))
      (node (ref "U$16") (pin "GND") (pinfunction "GND_GND") (pintype "bidirectional"))
      (node (ref "U$17") (pin "GND") (pinfunction "GND_GND") (pintype "bidirectional"))
      (node (ref "U$18") (pin "GND") (pinfunction "GND_GND") (pintype "bidirectional"))
      (node (ref "U$19") (pin "GND") (pinfunction "GND_GND") (pintype "bidirectional"))
      (node (ref "U$2") (pin "3") (pinfunction "DVSS_3") (pintype "bidirectional"))
      (node (ref "U$20") (pin "GND") (pinfunction "GND_GND") (pintype "bidirectional"))
      (node (ref "U$21") (pin "GND") (pinfunction "GND_GND") (pintype "bidirectional"))
      (node (ref "U$22") (pin "GND") (pinfunction "GND_GND") (pintype "bidirectional"))
      (node (ref "U$23") (pin "GND") (pinfunction "GND_GND") (pintype "bidirectional"))
      (node (ref "U$24") (pin "GND") (pinfunction "GND_GND") (pintype "bidirectional"))
      (node (ref "U$25") (pin "GND") (pinfunction "GND_GND") (pintype "bidirectional"))
      (node (ref "U$26") (pin "GND") (pinfunction "GND_GND") (pintype "bidirectional"))
      (node (ref "U$27") (pin "GND") (pinfunction "GND_GND") (pintype "bidirectional"))
      (node (ref "U$28") (pin "GND") (pinfunction "GND_GND") (pintype "bidirectional"))
      (node (ref "U$29") (pin "GND") (pinfunction "GND_GND") (pintype "bidirectional"))
      (node (ref "U$3") (pin "GND") (pinfunction "GND_GND") (pintype "bidirectional"))
      (node (ref "U$30") (pin "GND") (pinfunction "GND_GND") (pintype "bidirectional"))
      (node (ref "U$31") (pin "GND") (pinfunction "GND_GND") (pintype "bidirectional"))
      (node (ref "U$32") (pin "GND") (pinfunction "GND_GND") (pintype "bidirectional"))
      (node (ref "U$33") (pin "GND") (pinfunction "GND_GND") (pintype "bidirectional"))
      (node (ref "U$34") (pin "GND") (pinfunction "GND_GND") (pintype "bidirectional"))
      (node (ref "U$35") (pin "GND") (pinfunction "GND_GND") (pintype "bidirectional"))
      (node (ref "U$36") (pin "GND") (pinfunction "GND_GND") (pintype "bidirectional"))
      (node (ref "U$37") (pin "GND") (pinfunction "GND_GND") (pintype "bidirectional"))
      (node (ref "U$38") (pin "GND") (pinfunction "GND_GND") (pintype "bidirectional"))
      (node (ref "U$39") (pin "GND") (pinfunction "GND_GND") (pintype "bidirectional"))
      (node (ref "U$4") (pin "GND") (pinfunction "GND_GND") (pintype "bidirectional"))
      (node (ref "U$40") (pin "GND") (pinfunction "GND_GND") (pintype "bidirectional"))
      (node (ref "U$41") (pin "GND") (pinfunction "GND_GND") (pintype "bidirectional"))
      (node (ref "U$42") (pin "GND") (pinfunction "GND_GND") (pintype "bidirectional"))
      (node (ref "U$43") (pin "GND") (pinfunction "GND_GND") (pintype "bidirectional"))
      (node (ref "U$44") (pin "GND") (pinfunction "GND_GND") (pintype "bidirectional"))
      (node (ref "U$45") (pin "GND") (pinfunction "GND_GND") (pintype "bidirectional"))
      (node (ref "U$46") (pin "GND") (pinfunction "GND_GND") (pintype "bidirectional"))
      (node (ref "U$47") (pin "GND") (pinfunction "GND_GND") (pintype "bidirectional"))
      (node (ref "U$48") (pin "GND") (pinfunction "GND_GND") (pintype "bidirectional"))
      (node (ref "U$49") (pin "GND") (pinfunction "GND_GND") (pintype "bidirectional"))
      (node (ref "U$5") (pin "GND") (pinfunction "GND_GND") (pintype "bidirectional"))
      (node (ref "U$50") (pin "GND") (pinfunction "GND_GND") (pintype "bidirectional"))
      (node (ref "U$51") (pin "GND") (pinfunction "GND_GND") (pintype "bidirectional"))
      (node (ref "U$6") (pin "GND") (pinfunction "GND_GND") (pintype "bidirectional"))
      (node (ref "U$7") (pin "GND") (pinfunction "GND_GND") (pintype "bidirectional"))
      (node (ref "U$8") (pin "GND") (pinfunction "GND_GND") (pintype "bidirectional"))
      (node (ref "U$9") (pin "GND") (pinfunction "GND_GND") (pintype "bidirectional"))
    )
    (net (code "32") (name "Net-(BAT1-+-PadPOSITIVE@1)") (class "Default")
      (node (ref "BAT1") (pin "POSITIVE@1") (pinfunction "+_POSITIVE@1") (pintype "power_in"))
      (node (ref "BAT1") (pin "POSITIVE@2") (pinfunction "+_POSITIVE@2") (pintype "power_in"))
      (node (ref "BAT1") (pin "POSITIVE@3") (pinfunction "+_POSITIVE@3") (pintype "power_in"))
      (node (ref "BAT1") (pin "POSITIVE@4") (pinfunction "+_POSITIVE@4") (pintype "power_in"))
      (node (ref "D1") (pin "ANODE") (pinfunction "ANODE_ANODE") (pintype "bidirectional"))
    )
    (net (code "33") (name "Net-(BAT1--)") (class "Default")
      (node (ref "BAT1") (pin "NEGATIVE") (pinfunction "-_NEGATIVE") (pintype "power_in"))
      (node (ref "BAT2") (pin "POSITIVE@1") (pinfunction "+_POSITIVE@1") (pintype "power_in"))
      (node (ref "BAT2") (pin "POSITIVE@2") (pinfunction "+_POSITIVE@2") (pintype "power_in"))
      (node (ref "BAT2") (pin "POSITIVE@3") (pinfunction "+_POSITIVE@3") (pintype "power_in"))
      (node (ref "BAT2") (pin "POSITIVE@4") (pinfunction "+_POSITIVE@4") (pintype "power_in"))
    )
    (net (code "34") (name "Net-(C1-PadP$2)") (class "Default")
      (node (ref "C1") (pin "P$2") (pinfunction "P$2_P$2") (pintype "passive"))
      (node (ref "RST") (pin "P$4") (pinfunction "P$4_P$4") (pintype "bidirectional"))
    )
    (net (code "35") (name "Net-(U$2-P2.0{slash}XOUT)") (class "Default")
      (node (ref "C5") (pin "P$1") (pinfunction "P$1_P$1") (pintype "passive"))
      (node (ref "U$2") (pin "1") (pinfunction "P2.0/XOUT_1") (pintype "bidirectional"))
      (node (ref "X1") (pin "P$2") (pinfunction "P$2_P$2") (pintype "bidirectional"))
    )
    (net (code "36") (name "Net-(U$2-P2.1{slash}XIN)") (class "Default")
      (node (ref "C6") (pin "P$1") (pinfunction "P$1_P$1") (pintype "passive"))
      (node (ref "U$2") (pin "2") (pinfunction "P2.1/XIN_2") (pintype "bidirectional"))
      (node (ref "X1") (pin "P$1") (pinfunction "P$1_P$1") (pintype "bidirectional"))
    )
    (net (code "37") (name "Net-(U$2-VREG)") (class "Default")
      (node (ref "C3") (pin "P$1") (pinfunction "P$1_P$1") (pintype "passive"))
      (node (ref "U$2") (pin "24") (pinfunction "VREG_24") (pintype "bidirectional"))
    )
    (net (code "38") (name "Net-(U$3-PadTX2)") (class "Default")
      (node (ref "U$3") (pin "TX2") (pinfunction "TX2_TX2") (pintype "bidirectional"))
      (node (ref "U$4") (pin "TX1") (pinfunction "TX1_TX1") (pintype "bidirectional"))
    )
    (net (code "39") (name "Net-(U$4-PadTX2)") (class "Default")
      (node (ref "U$4") (pin "TX2") (pinfunction "TX2_TX2") (pintype "bidirectional"))
      (node (ref "U$5") (pin "TX1") (pinfunction "TX1_TX1") (pintype "bidirectional"))
    )
    (net (code "40") (name "Net-(U$5-PadTX2)") (class "Default")
      (node (ref "U$5") (pin "TX2") (pinfunction "TX2_TX2") (pintype "bidirectional"))
      (node (ref "U$6") (pin "TX1") (pinfunction "TX1_TX1") (pintype "bidirectional"))
    )
    (net (code "41") (name "Net-(U$6-PadTX2)") (class "Default")
      (node (ref "U$6") (pin "TX2") (pinfunction "TX2_TX2") (pintype "bidirectional"))
      (node (ref "U$7") (pin "TX1") (pinfunction "TX1_TX1") (pintype "bidirectional"))
    )
    (net (code "42") (name "Net-(U$10-PadTX1)") (class "Default")
      (node (ref "U$10") (pin "TX1") (pinfunction "TX1_TX1") (pintype "bidirectional"))
      (node (ref "U$9") (pin "TX2") (pinfunction "TX2_TX2") (pintype "bidirectional"))
    )
    (net (code "43") (name "Net-(U$10-PadTX2)") (class "Default")
      (node (ref "U$10") (pin "TX2") (pinfunction "TX2_TX2") (pintype "bidirectional"))
      (node (ref "U$11") (pin "TX1") (pinfunction "TX1_TX1") (pintype "bidirectional"))
    )
    (net (code "44") (name "Net-(U$11-PadTX2)") (class "Default")
      (node (ref "U$11") (pin "TX2") (pinfunction "TX2_TX2") (pintype "bidirectional"))
      (node (ref "U$12") (pin "TX1") (pinfunction "TX1_TX1") (pintype "bidirectional"))
    )
    (net (code "45") (name "Net-(U$14-PadTX2)") (class "Default")
      (node (ref "U$14") (pin "TX2") (pinfunction "TX2_TX2") (pintype "bidirectional"))
      (node (ref "U$15") (pin "TX1") (pinfunction "TX1_TX1") (pintype "bidirectional"))
    )
    (net (code "46") (name "Net-(U$15-PadTX2)") (class "Default")
      (node (ref "U$15") (pin "TX2") (pinfunction "TX2_TX2") (pintype "bidirectional"))
      (node (ref "U$16") (pin "TX1") (pinfunction "TX1_TX1") (pintype "bidirectional"))
    )
    (net (code "47") (name "Net-(U$16-PadTX2)") (class "Default")
      (node (ref "U$16") (pin "TX2") (pinfunction "TX2_TX2") (pintype "bidirectional"))
      (node (ref "U$17") (pin "TX1") (pinfunction "TX1_TX1") (pintype "bidirectional"))
    )
    (net (code "48") (name "Net-(U$18-PadTX2)") (class "Default")
      (node (ref "U$18") (pin "TX2") (pinfunction "TX2_TX2") (pintype "bidirectional"))
      (node (ref "U$19") (pin "TX1") (pinfunction "TX1_TX1") (pintype "bidirectional"))
    )
    (net (code "49") (name "Net-(U$20-PadTX2)") (class "Default")
      (node (ref "U$20") (pin "TX2") (pinfunction "TX2_TX2") (pintype "bidirectional"))
      (node (ref "U$21") (pin "TX1") (pinfunction "TX1_TX1") (pintype "bidirectional"))
    )
    (net (code "50") (name "Net-(U$21-PadTX2)") (class "Default")
      (node (ref "U$21") (pin "TX2") (pinfunction "TX2_TX2") (pintype "bidirectional"))
      (node (ref "U$22") (pin "TX1") (pinfunction "TX1_TX1") (pintype "bidirectional"))
    )
    (net (code "51") (name "Net-(U$23-PadTX2)") (class "Default")
      (node (ref "U$23") (pin "TX2") (pinfunction "TX2_TX2") (pintype "bidirectional"))
      (node (ref "U$24") (pin "TX1") (pinfunction "TX1_TX1") (pintype "bidirectional"))
    )
    (net (code "52") (name "Net-(U$25-PadTX2)") (class "Default")
      (node (ref "U$25") (pin "TX2") (pinfunction "TX2_TX2") (pintype "bidirectional"))
      (node (ref "U$26") (pin "TX1") (pinfunction "TX1_TX1") (pintype "bidirectional"))
    )
    (net (code "53") (name "Net-(U$26-PadTX2)") (class "Default")
      (node (ref "U$26") (pin "TX2") (pinfunction "TX2_TX2") (pintype "bidirectional"))
      (node (ref "U$27") (pin "TX1") (pinfunction "TX1_TX1") (pintype "bidirectional"))
    )
    (net (code "54") (name "Net-(U$28-PadTX2)") (class "Default")
      (node (ref "U$28") (pin "TX2") (pinfunction "TX2_TX2") (pintype "bidirectional"))
      (node (ref "U$29") (pin "TX1") (pinfunction "TX1_TX1") (pintype "bidirectional"))
    )
    (net (code "55") (name "Net-(U$29-PadTX2)") (class "Default")
      (node (ref "U$29") (pin "TX2") (pinfunction "TX2_TX2") (pintype "bidirectional"))
      (node (ref "U$30") (pin "TX1") (pinfunction "TX1_TX1") (pintype "bidirectional"))
    )
    (net (code "56") (name "Net-(U$31-PadTX2)") (class "Default")
      (node (ref "U$31") (pin "TX2") (pinfunction "TX2_TX2") (pintype "bidirectional"))
      (node (ref "U$32") (pin "TX1") (pinfunction "TX1_TX1") (pintype "bidirectional"))
    )
    (net (code "57") (name "Net-(U$33-PadTX2)") (class "Default")
      (node (ref "U$33") (pin "TX2") (pinfunction "TX2_TX2") (pintype "bidirectional"))
      (node (ref "U$34") (pin "TX1") (pinfunction "TX1_TX1") (pintype "bidirectional"))
    )
    (net (code "58") (name "Net-(U$34-PadTX2)") (class "Default")
      (node (ref "U$34") (pin "TX2") (pinfunction "TX2_TX2") (pintype "bidirectional"))
      (node (ref "U$35") (pin "TX1") (pinfunction "TX1_TX1") (pintype "bidirectional"))
    )
    (net (code "59") (name "Net-(U$36-PadTX2)") (class "Default")
      (node (ref "U$36") (pin "TX2") (pinfunction "TX2_TX2") (pintype "bidirectional"))
      (node (ref "U$37") (pin "TX1") (pinfunction "TX1_TX1") (pintype "bidirectional"))
    )
    (net (code "60") (name "Net-(U$38-PadTX2)") (class "Default")
      (node (ref "U$38") (pin "TX2") (pinfunction "TX2_TX2") (pintype "bidirectional"))
      (node (ref "U$39") (pin "TX1") (pinfunction "TX1_TX1") (pintype "bidirectional"))
    )
    (net (code "61") (name "Net-(U$39-PadTX2)") (class "Default")
      (node (ref "U$39") (pin "TX2") (pinfunction "TX2_TX2") (pintype "bidirectional"))
      (node (ref "U$40") (pin "TX1") (pinfunction "TX1_TX1") (pintype "bidirectional"))
    )
    (net (code "62") (name "Net-(U$40-PadTX2)") (class "Default")
      (node (ref "U$40") (pin "TX2") (pinfunction "TX2_TX2") (pintype "bidirectional"))
      (node (ref "U$41") (pin "TX1") (pinfunction "TX1_TX1") (pintype "bidirectional"))
    )
    (net (code "63") (name "Net-(U$43-PadTX2)") (class "Default")
      (node (ref "U$43") (pin "TX2") (pinfunction "TX2_TX2") (pintype "bidirectional"))
      (node (ref "U$44") (pin "TX1") (pinfunction "TX1_TX1") (pintype "bidirectional"))
    )
    (net (code "64") (name "Net-(U$44-PadTX2)") (class "Default")
      (node (ref "U$44") (pin "TX2") (pinfunction "TX2_TX2") (pintype "bidirectional"))
      (node (ref "U$45") (pin "TX1") (pinfunction "TX1_TX1") (pintype "bidirectional"))
    )
    (net (code "65") (name "Net-(U$45-PadTX2)") (class "Default")
      (node (ref "U$45") (pin "TX2") (pinfunction "TX2_TX2") (pintype "bidirectional"))
      (node (ref "U$46") (pin "TX1") (pinfunction "TX1_TX1") (pintype "bidirectional"))
    )
    (net (code "66") (name "Net-(U$48-PadTX2)") (class "Default")
      (node (ref "U$48") (pin "TX2") (pinfunction "TX2_TX2") (pintype "bidirectional"))
      (node (ref "U$49") (pin "TX1") (pinfunction "TX1_TX1") (pintype "bidirectional"))
    )
    (net (code "67") (name "Net-(U$49-PadTX2)") (class "Default")
      (node (ref "U$49") (pin "TX2") (pinfunction "TX2_TX2") (pintype "bidirectional"))
      (node (ref "U$50") (pin "TX1") (pinfunction "TX1_TX1") (pintype "bidirectional"))
    )
    (net (code "68") (name "Net-(U$50-PadTX2)") (class "Default")
      (node (ref "U$50") (pin "TX2") (pinfunction "TX2_TX2") (pintype "bidirectional"))
      (node (ref "U$51") (pin "TX1") (pinfunction "TX1_TX1") (pintype "bidirectional"))
    )
    (net (code "69") (name "VCC") (class "Default")
      (node (ref "BAT3") (pin "POSITIVE@1") (pinfunction "+_POSITIVE@1") (pintype "power_in"))
      (node (ref "BAT3") (pin "POSITIVE@2") (pinfunction "+_POSITIVE@2") (pintype "power_in"))
      (node (ref "BAT3") (pin "POSITIVE@3") (pinfunction "+_POSITIVE@3") (pintype "power_in"))
      (node (ref "BAT3") (pin "POSITIVE@4") (pinfunction "+_POSITIVE@4") (pintype "power_in"))
      (node (ref "C2") (pin "P$1") (pinfunction "P$1_P$1") (pintype "passive"))
      (node (ref "C4") (pin "P$1") (pinfunction "P$1_P$1") (pintype "passive"))
      (node (ref "R1") (pin "P$1") (pinfunction "P$1_P$1") (pintype "passive"))
      (node (ref "U$2") (pin "4") (pinfunction "DVCC_4") (pintype "bidirectional"))
    )
    (net (code "70") (name "unconnected-(RST-PadP$1)") (class "Default")
      (node (ref "RST") (pin "P$1") (pinfunction "P$1_P$1") (pintype "bidirectional"))
    )
    (net (code "71") (name "unconnected-(U$7-PadTX2)") (class "Default")
      (node (ref "U$7") (pin "TX2") (pinfunction "TX2_TX2") (pintype "bidirectional"))
    )
    (net (code "72") (name "unconnected-(U$8-PadTX1)") (class "Default")
      (node (ref "U$8") (pin "TX1") (pinfunction "TX1_TX1") (pintype "bidirectional"))
    )
    (net (code "73") (name "unconnected-(U$12-PadTX2)") (class "Default")
      (node (ref "U$12") (pin "TX2") (pinfunction "TX2_TX2") (pintype "bidirectional"))
    )
    (net (code "74") (name "unconnected-(U$13-PadTX1)") (class "Default")
      (node (ref "U$13") (pin "TX1") (pinfunction "TX1_TX1") (pintype "bidirectional"))
    )
    (net (code "75") (name "unconnected-(U$17-PadTX2)") (class "Default")
      (node (ref "U$17") (pin "TX2") (pinfunction "TX2_TX2") (pintype "bidirectional"))
    )
    (net (code "76") (name "unconnected-(U$18-PadTX1)") (class "Default")
      (node (ref "U$18") (pin "TX1") (pinfunction "TX1_TX1") (pintype "bidirectional"))
    )
    (net (code "77") (name "unconnected-(U$22-PadTX2)") (class "Default")
      (node (ref "U$22") (pin "TX2") (pinfunction "TX2_TX2") (pintype "bidirectional"))
    )
    (net (code "78") (name "unconnected-(U$23-PadTX1)") (class "Default")
      (node (ref "U$23") (pin "TX1") (pinfunction "TX1_TX1") (pintype "bidirectional"))
    )
    (net (code "79") (name "unconnected-(U$27-PadTX2)") (class "Default")
      (node (ref "U$27") (pin "TX2") (pinfunction "TX2_TX2") (pintype "bidirectional"))
    )
    (net (code "80") (name "unconnected-(U$28-PadTX1)") (class "Default")
      (node (ref "U$28") (pin "TX1") (pinfunction "TX1_TX1") (pintype "bidirectional"))
    )
    (net (code "81") (name "unconnected-(U$32-PadTX2)") (class "Default")
      (node (ref "U$32") (pin "TX2") (pinfunction "TX2_TX2") (pintype "bidirectional"))
    )
    (net (code "82") (name "unconnected-(U$33-PadTX1)") (class "Default")
      (node (ref "U$33") (pin "TX1") (pinfunction "TX1_TX1") (pintype "bidirectional"))
    )
    (net (code "83") (name "unconnected-(U$37-PadTX2)") (class "Default")
      (node (ref "U$37") (pin "TX2") (pinfunction "TX2_TX2") (pintype "bidirectional"))
    )
    (net (code "84") (name "unconnected-(U$38-PadTX1)") (class "Default")
      (node (ref "U$38") (pin "TX1") (pinfunction "TX1_TX1") (pintype "bidirectional"))
    )
    (net (code "85") (name "unconnected-(U$42-PadTX2)") (class "Default")
      (node (ref "U$42") (pin "TX2") (pinfunction "TX2_TX2") (pintype "bidirectional"))
    )
    (net (code "86") (name "unconnected-(U$43-PadTX1)") (class "Default")
      (node (ref "U$43") (pin "TX1") (pinfunction "TX1_TX1") (pintype "bidirectional"))
    )
    (net (code "87") (name "unconnected-(U$47-PadTX2)") (class "Default")
      (node (ref "U$47") (pin "TX2") (pinfunction "TX2_TX2") (pintype "bidirectional"))
    )
    (net (code "88") (name "unconnected-(U$48-PadTX1)") (class "Default")
      (node (ref "U$48") (pin "TX1") (pinfunction "TX1_TX1") (pintype "bidirectional"))
    )
  )
)
